# ATMegaBoard.net
KiCad netlist of a schematic drawn in EAGLE
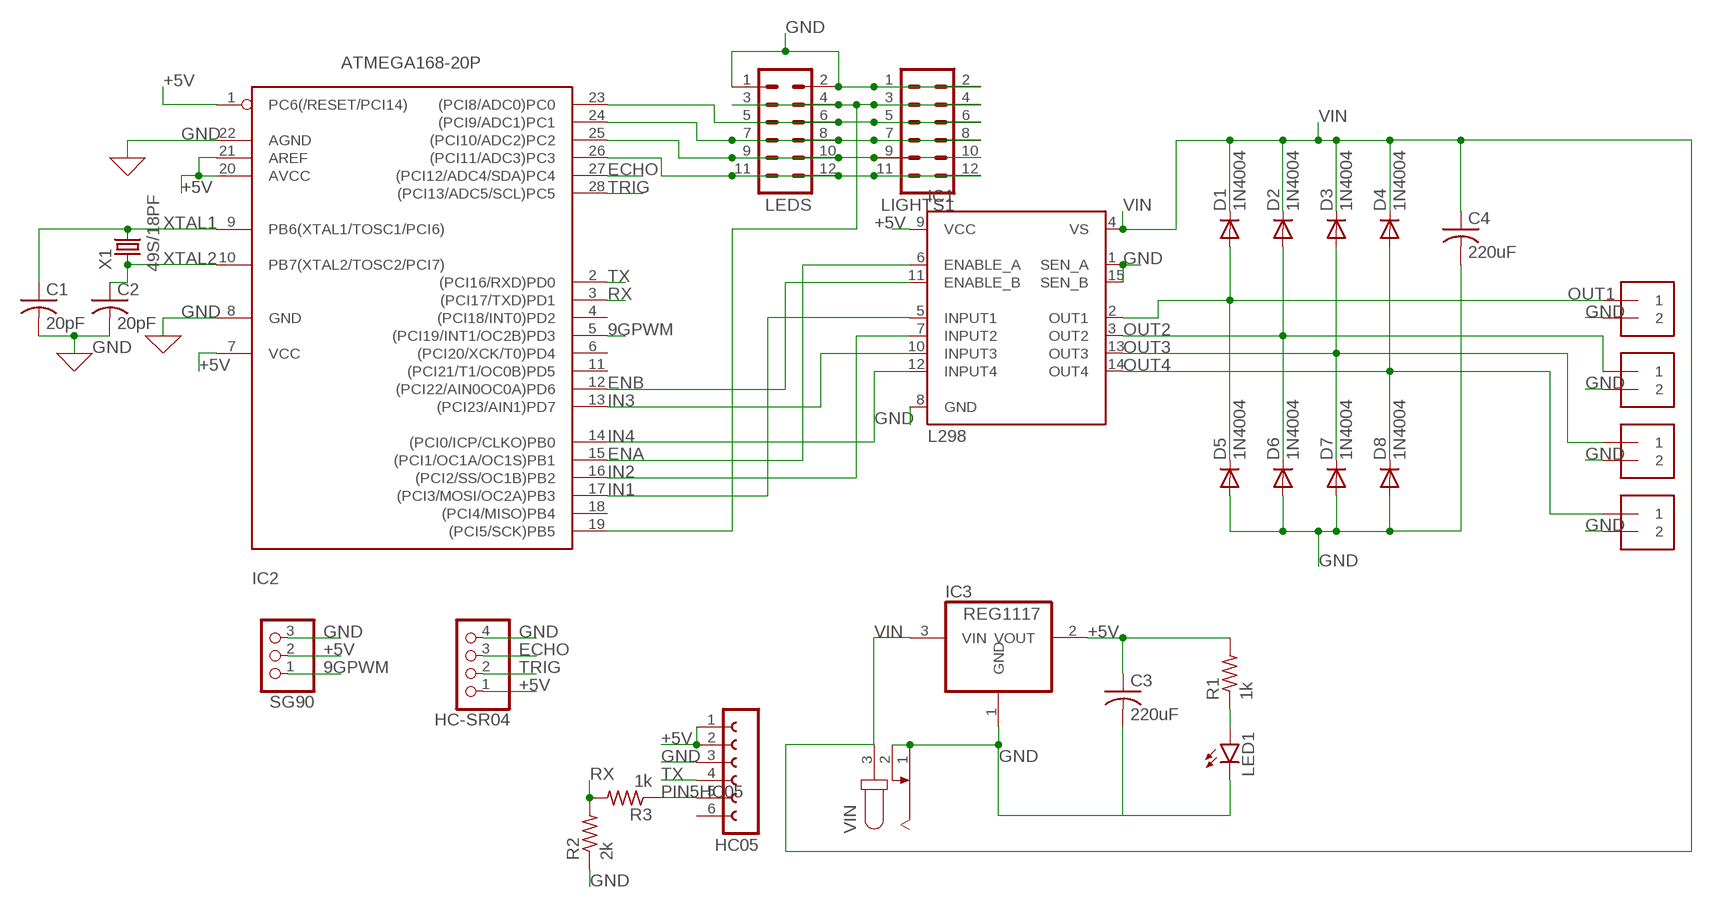
[diagram p0: schematic, sheet 1]

(export (version "E")
  (design (tool "Eeschema 10.0.6"))
  (components
    (comp (ref "C1")
      (value "20pF")
      (footprint "eagle-import:C050-024X044")
      (libsource (lib "eagle-import") (part "C-US050-024X044"))
    )
    (comp (ref "C2")
      (value "20pF")
      (footprint "eagle-import:C050-024X044")
      (libsource (lib "eagle-import") (part "C-US050-024X044"))
    )
    (comp (ref "C3")
      (value "220uF")
      (footprint "eagle-import:C050-024X044")
      (libsource (lib "eagle-import") (part "C-US050-024X044"))
    )
    (comp (ref "C4")
      (value "220uF")
      (footprint "eagle-import:C050-024X044")
      (libsource (lib "eagle-import") (part "C-US050-024X044"))
    )
    (comp (ref "D1")
      (value "1N4004")
      (footprint "eagle-import:DO41-10")
      (libsource (lib "eagle-import") (part "1N4004"))
    )
    (comp (ref "D2")
      (value "1N4004")
      (footprint "eagle-import:DO41-10")
      (libsource (lib "eagle-import") (part "1N4004"))
    )
    (comp (ref "D3")
      (value "1N4004")
      (footprint "eagle-import:DO41-10")
      (libsource (lib "eagle-import") (part "1N4004"))
    )
    (comp (ref "D4")
      (value "1N4004")
      (footprint "eagle-import:DO41-10")
      (libsource (lib "eagle-import") (part "1N4004"))
    )
    (comp (ref "D5")
      (value "1N4004")
      (footprint "eagle-import:DO41-10")
      (libsource (lib "eagle-import") (part "1N4004"))
    )
    (comp (ref "D6")
      (value "1N4004")
      (footprint "eagle-import:DO41-10")
      (libsource (lib "eagle-import") (part "1N4004"))
    )
    (comp (ref "D7")
      (value "1N4004")
      (footprint "eagle-import:DO41-10")
      (libsource (lib "eagle-import") (part "1N4004"))
    )
    (comp (ref "D8")
      (value "1N4004")
      (footprint "eagle-import:DO41-10")
      (libsource (lib "eagle-import") (part "1N4004"))
    )
    (comp (ref "HC-SR04")
      (value "PINHD-1X4")
      (footprint "eagle-import:1X04")
      (libsource (lib "eagle-import") (part "PINHD-1X4"))
    )
    (comp (ref "HC05")
      (value "FE06W")
      (footprint "eagle-import:FE06W")
      (libsource (lib "eagle-import") (part "FE06W"))
    )
    (comp (ref "IC1")
      (value "L298")
      (footprint "eagle-import:MULTIWATT-15")
      (fields (field (name "MPN") "L298N"))
      (libsource (lib "eagle-import") (part "L298"))
    )
    (comp (ref "IC2")
      (value "ATMEGA168-20P")
      (footprint "eagle-import:DIL28-3")
      (libsource (lib "eagle-import") (part "ATMEGA168P-20"))
    )
    (comp (ref "IC3")
      (value "REG1117")
      (footprint "eagle-import:SOT223")
      (libsource (lib "eagle-import") (part "REG1117"))
    )
    (comp (ref "LED1")
      (value "LED5MM")
      (footprint "eagle-import:LED5MM")
      (libsource (lib "eagle-import") (part "LED5MM"))
    )
    (comp (ref "LEDS")
      (value "MA06-2")
      (footprint "eagle-import:MA06-2")
      (libsource (lib "eagle-import") (part "MA06-2"))
    )
    (comp (ref "LIGHTS1")
      (value "MA06-2")
      (footprint "eagle-import:MA06-2")
      (libsource (lib "eagle-import") (part "MA06-2"))
    )
    (comp (ref "OUT1")
      (value "1X2-3.5MM")
      (footprint "eagle-import:1X2-3.5MM")
      (libsource (lib "eagle-import") (part "1X2-3.5MM"))
    )
    (comp (ref "OUT2")
      (value "1X2-3.5MM")
      (footprint "eagle-import:1X2-3.5MM")
      (libsource (lib "eagle-import") (part "1X2-3.5MM"))
    )
    (comp (ref "OUT3")
      (value "1X2-3.5MM")
      (footprint "eagle-import:1X2-3.5MM")
      (libsource (lib "eagle-import") (part "1X2-3.5MM"))
    )
    (comp (ref "OUT4")
      (value "1X2-3.5MM")
      (footprint "eagle-import:1X2-3.5MM")
      (libsource (lib "eagle-import") (part "1X2-3.5MM"))
    )
    (comp (ref "R1")
      (value "1k")
      (footprint "eagle-import:0207_10")
      (libsource (lib "eagle-import") (part "R-US_0207/10"))
    )
    (comp (ref "R2")
      (value "2k")
      (footprint "eagle-import:0207_10")
      (libsource (lib "eagle-import") (part "R-US_0207/10"))
    )
    (comp (ref "R3")
      (value "1k")
      (footprint "eagle-import:0207_10")
      (libsource (lib "eagle-import") (part "R-US_0207/10"))
    )
    (comp (ref "SG90")
      (value "PINHD-1X3")
      (footprint "eagle-import:1X03")
      (libsource (lib "eagle-import") (part "PINHD-1X3"))
    )
    (comp (ref "VIN")
      (value "JACK-PLUG1")
      (footprint "eagle-import:SPC4078")
      (libsource (lib "eagle-import") (part "JACK-PLUG1"))
    )
    (comp (ref "X1")
      (value "49S/18PF")
      (footprint "eagle-import:XTAL_HC49")
      (fields (field (name "MANUFACTURER") "Xinhunjing ") (field (name "CREATED_BY") "PCBLayout.com"))
      (libsource (lib "eagle-import") (part "49S/18PF"))
    )
  )
  (nets
    (net (code "1") (name "/+5V") (class "Default")
      (node (ref "C3") (pin "1") (pinfunction "1_1") (pintype "passive"))
      (node (ref "HC-SR04") (pin "1") (pinfunction "1_1") (pintype "passive"))
      (node (ref "HC05") (pin "1") (pinfunction "1_1") (pintype "passive"))
      (node (ref "HC05") (pin "2") (pinfunction "2_2") (pintype "passive"))
      (node (ref "IC1") (pin "9") (pinfunction "VCC_9") (pintype "power_in"))
      (node (ref "IC2") (pin "1") (pinfunction "PC6(/RESET/PCI14)_1") (pintype "bidirectional"))
      (node (ref "IC2") (pin "20") (pinfunction "AVCC_20") (pintype "bidirectional"))
      (node (ref "IC2") (pin "21") (pinfunction "AREF_21") (pintype "bidirectional"))
      (node (ref "IC2") (pin "7") (pinfunction "VCC_7") (pintype "bidirectional"))
      (node (ref "IC3") (pin "2") (pinfunction "VOUT_2") (pintype "output"))
      (node (ref "R1") (pin "2") (pinfunction "2_2") (pintype "passive"))
      (node (ref "SG90") (pin "2") (pinfunction "2_2") (pintype "passive"))
    )
    (net (code "2") (name "/9GPWM") (class "Default")
      (node (ref "IC2") (pin "5") (pinfunction "(PCI19/INT1/OC2B)PD3_5") (pintype "bidirectional"))
      (node (ref "SG90") (pin "1") (pinfunction "1_1") (pintype "passive"))
    )
    (net (code "3") (name "/ECHO") (class "Default")
      (node (ref "HC-SR04") (pin "3") (pinfunction "3_3") (pintype "passive"))
      (node (ref "IC2") (pin "27") (pinfunction "(PCI12/ADC4/SDA)PC4_27") (pintype "bidirectional"))
    )
    (net (code "4") (name "/ENA") (class "Default")
      (node (ref "IC1") (pin "6") (pinfunction "ENABLE_A_6") (pintype "input"))
      (node (ref "IC2") (pin "15") (pinfunction "(PCI1/OC1A/OC1S)PB1_15") (pintype "bidirectional"))
    )
    (net (code "5") (name "/ENB") (class "Default")
      (node (ref "IC1") (pin "11") (pinfunction "ENABLE_B_11") (pintype "input"))
      (node (ref "IC2") (pin "12") (pinfunction "(PCI22/AIN0OC0A)PD6_12") (pintype "bidirectional"))
    )
    (net (code "6") (name "/IN1") (class "Default")
      (node (ref "IC1") (pin "5") (pinfunction "INPUT1_5") (pintype "input"))
      (node (ref "IC2") (pin "17") (pinfunction "(PCI3/MOSI/OC2A)PB3_17") (pintype "bidirectional"))
    )
    (net (code "7") (name "/IN2") (class "Default")
      (node (ref "IC1") (pin "7") (pinfunction "INPUT2_7") (pintype "input"))
      (node (ref "IC2") (pin "16") (pinfunction "(PCI2/SS/OC1B)PB2_16") (pintype "bidirectional"))
    )
    (net (code "8") (name "/IN3") (class "Default")
      (node (ref "IC1") (pin "10") (pinfunction "INPUT3_10") (pintype "input"))
      (node (ref "IC2") (pin "13") (pinfunction "(PCI23/AIN1)PD7_13") (pintype "bidirectional"))
    )
    (net (code "9") (name "/IN4") (class "Default")
      (node (ref "IC1") (pin "12") (pinfunction "INPUT4_12") (pintype "input"))
      (node (ref "IC2") (pin "14") (pinfunction "(PCI0/ICP/CLKO)PB0_14") (pintype "bidirectional"))
    )
    (net (code "10") (name "/OUT1") (class "Default")
      (node (ref "D1") (pin "A") (pinfunction "A_A") (pintype "passive"))
      (node (ref "D5") (pin "C") (pinfunction "C_C") (pintype "passive"))
      (node (ref "IC1") (pin "2") (pinfunction "OUT1_2") (pintype "output"))
      (node (ref "OUT1") (pin "1") (pinfunction "1_1") (pintype "passive"))
    )
    (net (code "11") (name "/OUT2") (class "Default")
      (node (ref "D2") (pin "A") (pinfunction "A_A") (pintype "passive"))
      (node (ref "D6") (pin "C") (pinfunction "C_C") (pintype "passive"))
      (node (ref "IC1") (pin "3") (pinfunction "OUT2_3") (pintype "output"))
      (node (ref "OUT2") (pin "1") (pinfunction "1_1") (pintype "passive"))
    )
    (net (code "12") (name "/OUT3") (class "Default")
      (node (ref "D3") (pin "A") (pinfunction "A_A") (pintype "passive"))
      (node (ref "D7") (pin "C") (pinfunction "C_C") (pintype "passive"))
      (node (ref "IC1") (pin "13") (pinfunction "OUT3_13") (pintype "output"))
      (node (ref "OUT3") (pin "1") (pinfunction "1_1") (pintype "passive"))
    )
    (net (code "13") (name "/OUT4") (class "Default")
      (node (ref "D4") (pin "A") (pinfunction "A_A") (pintype "passive"))
      (node (ref "D8") (pin "C") (pinfunction "C_C") (pintype "passive"))
      (node (ref "IC1") (pin "14") (pinfunction "OUT4_14") (pintype "output"))
      (node (ref "OUT4") (pin "1") (pinfunction "1_1") (pintype "passive"))
    )
    (net (code "14") (name "/PIN5HC05") (class "Default")
      (node (ref "HC05") (pin "5") (pinfunction "5_5") (pintype "passive"))
      (node (ref "R3") (pin "1") (pinfunction "1_1") (pintype "passive"))
    )
    (net (code "15") (name "/RX") (class "Default")
      (node (ref "IC2") (pin "3") (pinfunction "(PCI17/TXD)PD1_3") (pintype "bidirectional"))
      (node (ref "R2") (pin "2") (pinfunction "2_2") (pintype "passive"))
      (node (ref "R3") (pin "2") (pinfunction "2_2") (pintype "passive"))
    )
    (net (code "16") (name "/TRIG") (class "Default")
      (node (ref "HC-SR04") (pin "2") (pinfunction "2_2") (pintype "passive"))
      (node (ref "IC2") (pin "28") (pinfunction "(PCI13/ADC5/SCL)PC5_28") (pintype "bidirectional"))
    )
    (net (code "17") (name "/TX") (class "Default")
      (node (ref "HC05") (pin "4") (pinfunction "4_4") (pintype "passive"))
      (node (ref "IC2") (pin "2") (pinfunction "(PCI16/RXD)PD0_2") (pintype "bidirectional"))
    )
    (net (code "18") (name "/VIN") (class "Default")
      (node (ref "C4") (pin "1") (pinfunction "1_1") (pintype "passive"))
      (node (ref "D1") (pin "C") (pinfunction "C_C") (pintype "passive"))
      (node (ref "D2") (pin "C") (pinfunction "C_C") (pintype "passive"))
      (node (ref "D3") (pin "C") (pinfunction "C_C") (pintype "passive"))
      (node (ref "D4") (pin "C") (pinfunction "C_C") (pintype "passive"))
      (node (ref "IC1") (pin "4") (pinfunction "VS_4") (pintype "power_in"))
      (node (ref "IC3") (pin "3") (pinfunction "VIN_3") (pintype "input"))
      (node (ref "VIN") (pin "3") (pinfunction "3_3") (pintype "passive"))
    )
    (net (code "19") (name "/XTAL1") (class "Default")
      (node (ref "C1") (pin "1") (pinfunction "1_1") (pintype "passive"))
      (node (ref "IC2") (pin "9") (pinfunction "PB6(XTAL1/TOSC1/PCI6)_9") (pintype "bidirectional"))
      (node (ref "X1") (pin "2") (pinfunction "2_2") (pintype "passive"))
    )
    (net (code "20") (name "/XTAL2") (class "Default")
      (node (ref "C2") (pin "1") (pinfunction "1_1") (pintype "passive"))
      (node (ref "IC2") (pin "10") (pinfunction "PB7(XTAL2/TOSC2/PCI7)_10") (pintype "bidirectional"))
      (node (ref "X1") (pin "1") (pinfunction "1_1") (pintype "passive"))
    )
    (net (code "21") (name "GND") (class "Default")
      (node (ref "C1") (pin "2") (pinfunction "2_2") (pintype "passive"))
      (node (ref "C2") (pin "2") (pinfunction "2_2") (pintype "passive"))
      (node (ref "C3") (pin "2") (pinfunction "2_2") (pintype "passive"))
      (node (ref "C4") (pin "2") (pinfunction "2_2") (pintype "passive"))
      (node (ref "D5") (pin "A") (pinfunction "A_A") (pintype "passive"))
      (node (ref "D6") (pin "A") (pinfunction "A_A") (pintype "passive"))
      (node (ref "D7") (pin "A") (pinfunction "A_A") (pintype "passive"))
      (node (ref "D8") (pin "A") (pinfunction "A_A") (pintype "passive"))
      (node (ref "HC-SR04") (pin "4") (pinfunction "4_4") (pintype "passive"))
      (node (ref "HC05") (pin "3") (pinfunction "3_3") (pintype "passive"))
      (node (ref "IC1") (pin "1") (pinfunction "SEN_A_1") (pintype "input"))
      (node (ref "IC1") (pin "15") (pinfunction "SEN_B_15") (pintype "input"))
      (node (ref "IC1") (pin "8") (pinfunction "GND_8") (pintype "power_in"))
      (node (ref "IC2") (pin "22") (pinfunction "AGND_22") (pintype "bidirectional"))
      (node (ref "IC2") (pin "8") (pinfunction "GND_8") (pintype "bidirectional"))
      (node (ref "IC3") (pin "1") (pinfunction "GND_1") (pintype "power_in"))
      (node (ref "LED1") (pin "K") (pinfunction "C_K") (pintype "passive"))
      (node (ref "LEDS") (pin "1") (pinfunction "1_1") (pintype "passive"))
      (node (ref "LEDS") (pin "2") (pinfunction "2_2") (pintype "passive"))
      (node (ref "LIGHTS1") (pin "1") (pinfunction "1_1") (pintype "passive"))
      (node (ref "LIGHTS1") (pin "2") (pinfunction "2_2") (pintype "passive"))
      (node (ref "OUT1") (pin "2") (pinfunction "2_2") (pintype "passive"))
      (node (ref "OUT2") (pin "2") (pinfunction "2_2") (pintype "passive"))
      (node (ref "OUT3") (pin "2") (pinfunction "2_2") (pintype "passive"))
      (node (ref "OUT4") (pin "2") (pinfunction "2_2") (pintype "passive"))
      (node (ref "R2") (pin "1") (pinfunction "1_1") (pintype "passive"))
      (node (ref "SG90") (pin "3") (pinfunction "3_3") (pintype "passive"))
      (node (ref "VIN") (pin "1") (pinfunction "1_1") (pintype "passive"))
      (node (ref "VIN") (pin "2") (pinfunction "2_2") (pintype "passive"))
    )
    (net (code "22") (name "Net-(IC2-(PCI5{slash}SCK)PB5)") (class "Default")
      (node (ref "IC2") (pin "19") (pinfunction "(PCI5/SCK)PB5_19") (pintype "bidirectional"))
      (node (ref "LEDS") (pin "3") (pinfunction "3_3") (pintype "passive"))
      (node (ref "LEDS") (pin "4") (pinfunction "4_4") (pintype "passive"))
      (node (ref "LIGHTS1") (pin "3") (pinfunction "3_3") (pintype "passive"))
      (node (ref "LIGHTS1") (pin "4") (pinfunction "4_4") (pintype "passive"))
    )
    (net (code "23") (name "Net-(IC2-(PCI8{slash}ADC0)PC0)") (class "Default")
      (node (ref "IC2") (pin "23") (pinfunction "(PCI8/ADC0)PC0_23") (pintype "bidirectional"))
      (node (ref "LEDS") (pin "5") (pinfunction "5_5") (pintype "passive"))
      (node (ref "LEDS") (pin "6") (pinfunction "6_6") (pintype "passive"))
      (node (ref "LIGHTS1") (pin "5") (pinfunction "5_5") (pintype "passive"))
      (node (ref "LIGHTS1") (pin "6") (pinfunction "6_6") (pintype "passive"))
    )
    (net (code "24") (name "Net-(IC2-(PCI9{slash}ADC1)PC1)") (class "Default")
      (node (ref "IC2") (pin "24") (pinfunction "(PCI9/ADC1)PC1_24") (pintype "bidirectional"))
      (node (ref "LEDS") (pin "7") (pinfunction "7_7") (pintype "passive"))
      (node (ref "LEDS") (pin "8") (pinfunction "8_8") (pintype "passive"))
      (node (ref "LIGHTS1") (pin "7") (pinfunction "7_7") (pintype "passive"))
      (node (ref "LIGHTS1") (pin "8") (pinfunction "8_8") (pintype "passive"))
    )
    (net (code "25") (name "Net-(IC2-(PCI10{slash}ADC2)PC2)") (class "Default")
      (node (ref "IC2") (pin "25") (pinfunction "(PCI10/ADC2)PC2_25") (pintype "bidirectional"))
      (node (ref "LEDS") (pin "10") (pinfunction "10_10") (pintype "passive"))
      (node (ref "LEDS") (pin "9") (pinfunction "9_9") (pintype "passive"))
      (node (ref "LIGHTS1") (pin "10") (pinfunction "10_10") (pintype "passive"))
      (node (ref "LIGHTS1") (pin "9") (pinfunction "9_9") (pintype "passive"))
    )
    (net (code "26") (name "Net-(IC2-(PCI11{slash}ADC3)PC3)") (class "Default")
      (node (ref "IC2") (pin "26") (pinfunction "(PCI11/ADC3)PC3_26") (pintype "bidirectional"))
      (node (ref "LEDS") (pin "11") (pinfunction "11_11") (pintype "passive"))
      (node (ref "LEDS") (pin "12") (pinfunction "12_12") (pintype "passive"))
      (node (ref "LIGHTS1") (pin "11") (pinfunction "11_11") (pintype "passive"))
      (node (ref "LIGHTS1") (pin "12") (pinfunction "12_12") (pintype "passive"))
    )
    (net (code "27") (name "Net-(LED1-PadA)") (class "Default")
      (node (ref "LED1") (pin "A") (pinfunction "A_A") (pintype "passive"))
      (node (ref "R1") (pin "1") (pinfunction "1_1") (pintype "passive"))
    )
    (net (code "28") (name "unconnected-(HC05-Pad6)") (class "Default")
      (node (ref "HC05") (pin "6") (pinfunction "6_6") (pintype "passive"))
    )
    (net (code "29") (name "unconnected-(IC2-(PCI4{slash}MISO)PB4-Pad18)") (class "Default")
      (node (ref "IC2") (pin "18") (pinfunction "(PCI4/MISO)PB4_18") (pintype "bidirectional"))
    )
    (net (code "30") (name "unconnected-(IC2-(PCI18{slash}INT0)PD2-Pad4)") (class "Default")
      (node (ref "IC2") (pin "4") (pinfunction "(PCI18/INT0)PD2_4") (pintype "bidirectional"))
    )
    (net (code "31") (name "unconnected-(IC2-(PCI20{slash}XCK{slash}T0)PD4-Pad6)") (class "Default")
      (node (ref "IC2") (pin "6") (pinfunction "(PCI20/XCK/T0)PD4_6") (pintype "bidirectional"))
    )
    (net (code "32") (name "unconnected-(IC2-(PCI21{slash}T1{slash}OC0B)PD5-Pad11)") (class "Default")
      (node (ref "IC2") (pin "11") (pinfunction "(PCI21/T1/OC0B)PD5_11") (pintype "bidirectional"))
    )
  )
)
